# USB_2_High_Speed.net
KiCad netlist of a schematic drawn in Altium Designer
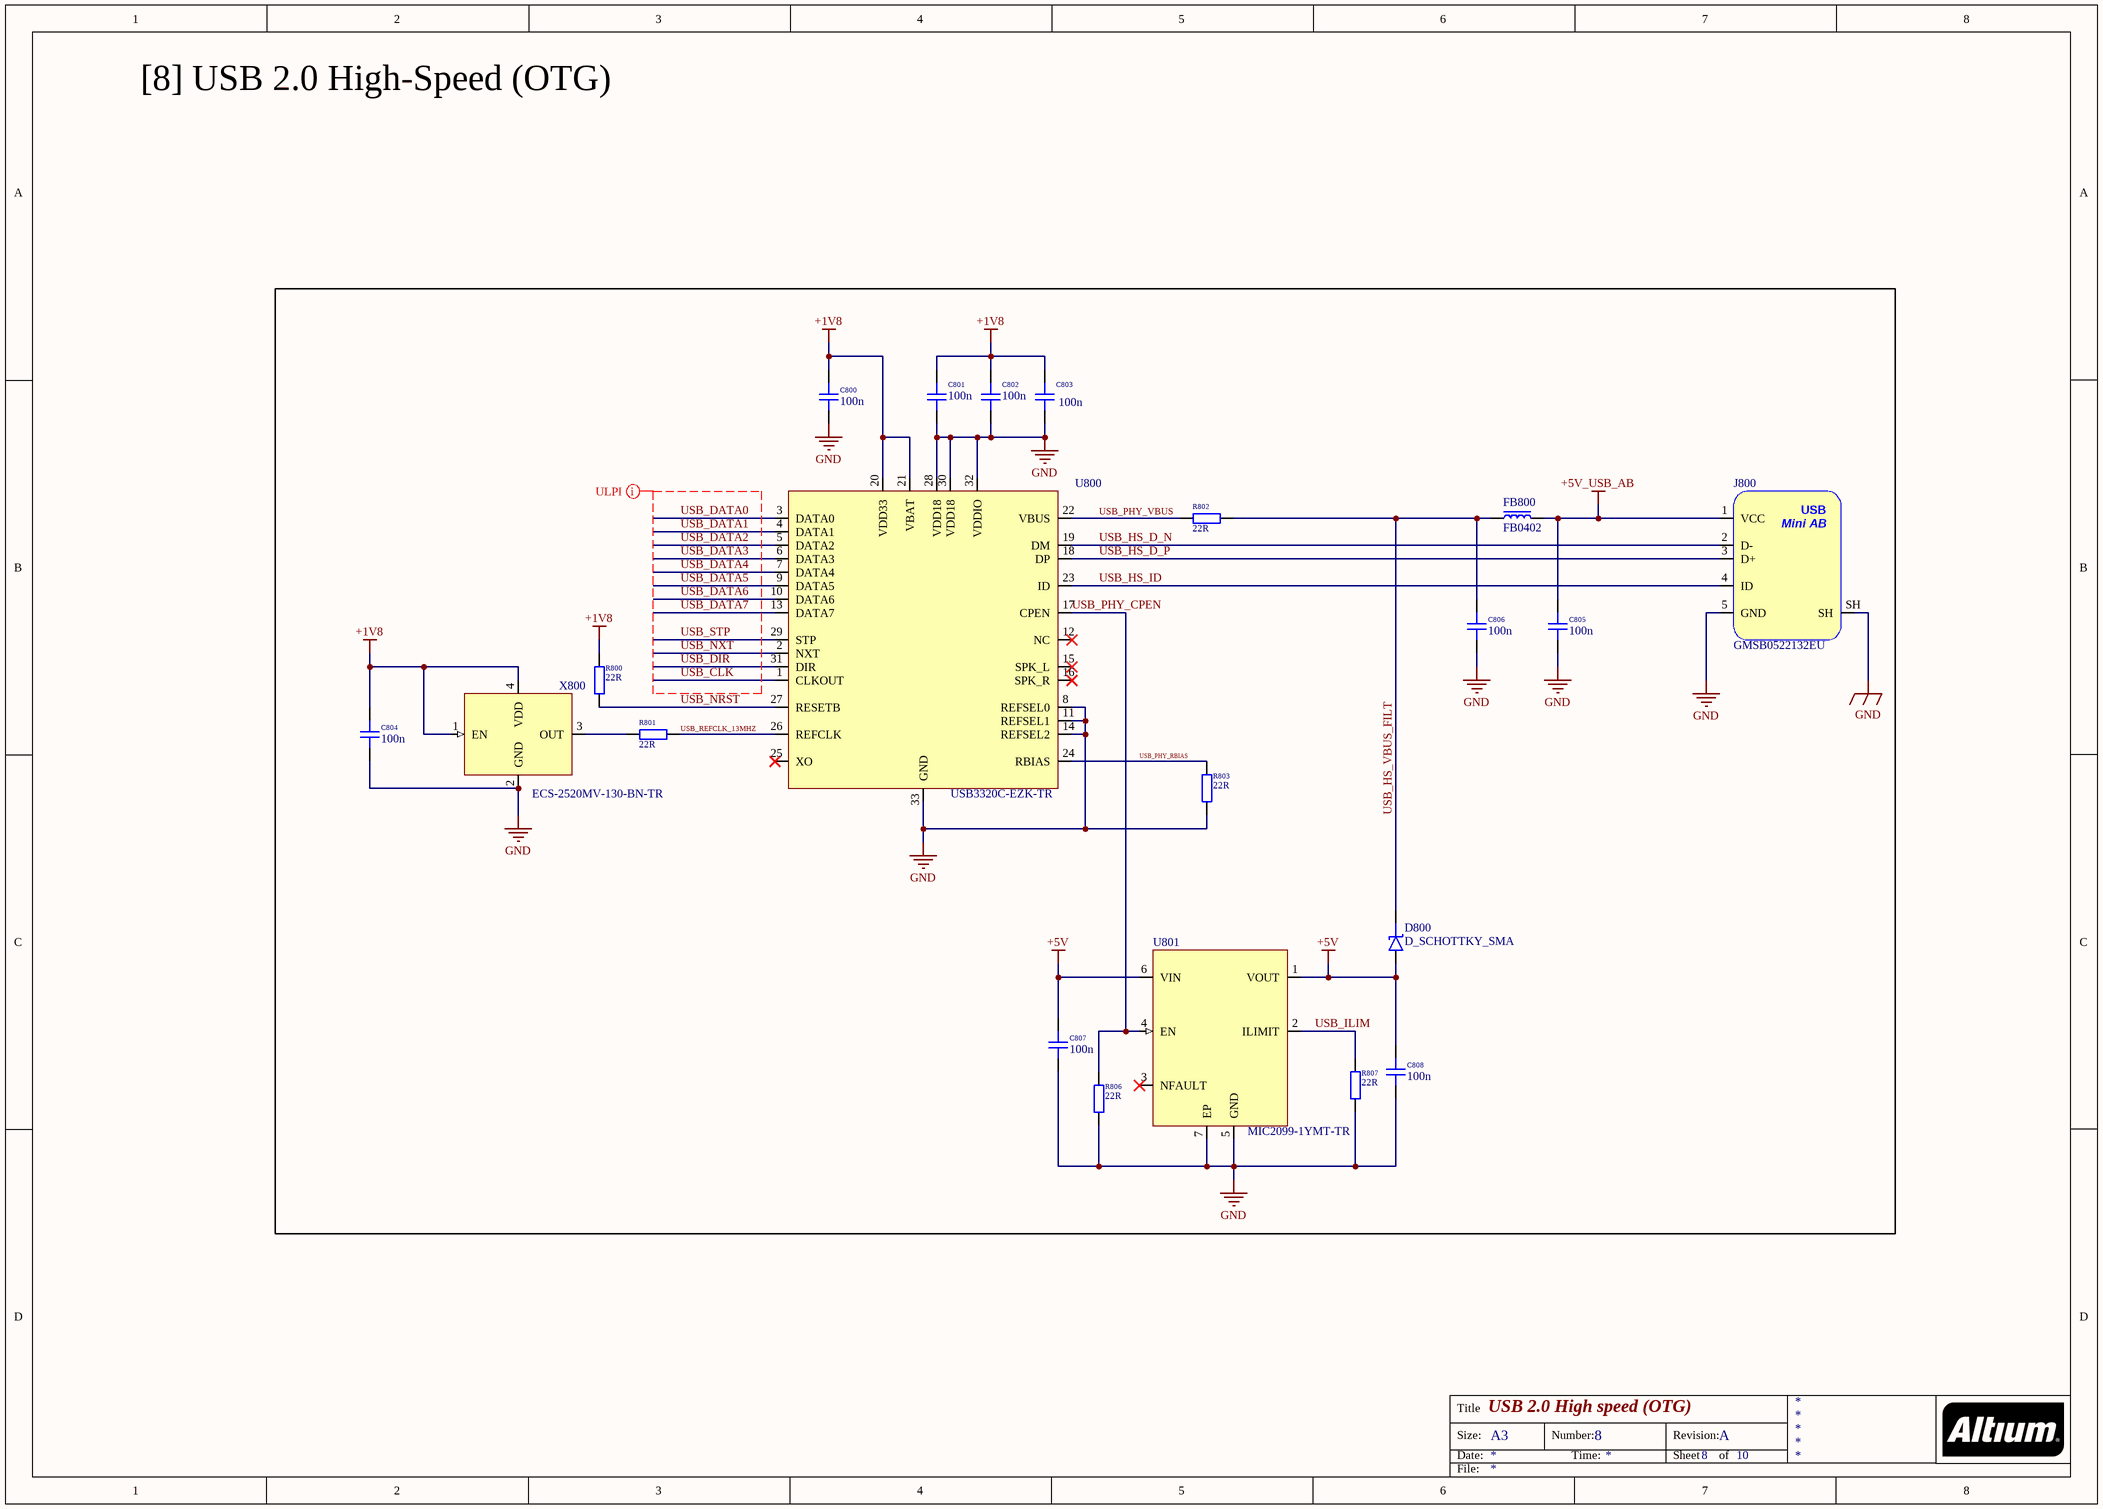
[diagram p0: USB 2 High Speed (OTG).SchDoc]

(export (version "E")
  (design (tool "Eeschema 10.0.6"))
  (components
    (comp (ref "C800")
      (value "100n")
      (footprint "CAP_1210")
      (description "Capacitor SMD 1210")
      (libsource (lib "Schematic-Lib-PhilsLab") (part "CAP_1210"))
    )
    (comp (ref "C801")
      (value "100n")
      (footprint "CAP_1210")
      (description "Capacitor SMD 1210")
      (libsource (lib "Schematic-Lib-PhilsLab") (part "CAP_1210"))
    )
    (comp (ref "C802")
      (value "100n")
      (footprint "CAP_1210")
      (description "Capacitor SMD 1210")
      (libsource (lib "Schematic-Lib-PhilsLab") (part "CAP_1210"))
    )
    (comp (ref "C803")
      (value "100n")
      (footprint "CAP_1210")
      (description "Capacitor SMD 1210")
      (libsource (lib "Schematic-Lib-PhilsLab") (part "CAP_1210"))
    )
    (comp (ref "C804")
      (value "100n")
      (footprint "CAP_1210")
      (description "Capacitor SMD 1210")
      (libsource (lib "Schematic-Lib-PhilsLab") (part "CAP_1210"))
    )
    (comp (ref "C805")
      (value "100n")
      (footprint "CAP_1210")
      (description "Capacitor SMD 1210")
      (libsource (lib "Schematic-Lib-PhilsLab") (part "CAP_1210"))
    )
    (comp (ref "C806")
      (value "100n")
      (footprint "CAP_1210")
      (description "Capacitor SMD 1210")
      (libsource (lib "Schematic-Lib-PhilsLab") (part "CAP_1210"))
    )
    (comp (ref "C807")
      (value "100n")
      (footprint "CAP_1210")
      (description "Capacitor SMD 1210")
      (libsource (lib "Schematic-Lib-PhilsLab") (part "CAP_1210"))
    )
    (comp (ref "C808")
      (value "100n")
      (footprint "CAP_1210")
      (description "Capacitor SMD 1210")
      (libsource (lib "Schematic-Lib-PhilsLab") (part "CAP_1210"))
    )
    (comp (ref "D800")
      (value "D_SCHOTTKY_SMA")
      (footprint "DO-214AC-2 (SMA)")
      (description "Diode Schottky SMD SMA (DO-214AA)")
      (libsource (lib "Schematic-Lib-PhilsLab") (part "D_SCHOTTKY_SMA"))
    )
    (comp (ref "FB800")
      (value "FB0402")
      (footprint "FB_0402")
      (description "Ferrite Bead SMD 0402")
      (libsource (lib "Schematic-Lib-PhilsLab") (part "FB_0402"))
    )
    (comp (ref "J800")
      (value "GMSB0522132EU")
      (footprint "GMSB0522132EU")
      (description "USB 2.0 Mini AB Receptacle Right Angle Through-Hole")
      (fields (field (name "MANUFACTURER") "Amphenol"))
      (libsource (lib "Schematic-Lib-PhilsLab") (part "GMSB0522132EU"))
    )
    (comp (ref "R800")
      (value "22R")
      (footprint "RES_0402")
      (description "Resistor SMD 0402")
      (libsource (lib "Schematic-Lib-PhilsLab") (part "RES_0402"))
    )
    (comp (ref "R801")
      (value "22R")
      (footprint "RES_0402")
      (description "Resistor SMD 0402")
      (libsource (lib "Schematic-Lib-PhilsLab") (part "RES_0402"))
    )
    (comp (ref "R802")
      (value "22R")
      (footprint "RES_0402")
      (description "Resistor SMD 0402")
      (libsource (lib "Schematic-Lib-PhilsLab") (part "RES_0402"))
    )
    (comp (ref "R803")
      (value "22R")
      (footprint "RES_0402")
      (description "Resistor SMD 0402")
      (libsource (lib "Schematic-Lib-PhilsLab") (part "RES_0402"))
    )
    (comp (ref "R806")
      (value "22R")
      (footprint "RES_0402")
      (description "Resistor SMD 0402")
      (libsource (lib "Schematic-Lib-PhilsLab") (part "RES_0402"))
    )
    (comp (ref "R807")
      (value "22R")
      (footprint "RES_0402")
      (description "Resistor SMD 0402")
      (libsource (lib "Schematic-Lib-PhilsLab") (part "RES_0402"))
    )
    (comp (ref "U800")
      (value "USB3320C-EZK-TR")
      (footprint "QFN-32-5x5x0.85mm")
      (description "Hi-Speed USB 2.0 ULPI Transceiver")
      (fields (field (name "MANUFACTURER") "Microchip"))
      (libsource (lib "Schematic-Lib-PhilsLab") (part "USB3320C-EZK-TR"))
    )
    (comp (ref "U801")
      (value "MIC2099-1YMT-TR")
      (footprint "TMLF-6-1_6X1_6")
      (description "Power Distribution Switch Resistor programmable current limit\r\n– 0.1A to 1.1A 2.5V-5.5V")
      (fields (field (name "MANUFACTURER") "Microchip"))
      (libsource (lib "Schematic-Lib-PhilsLab") (part "MIC2099-1YMT-TR"))
    )
    (comp (ref "X800")
      (value "ECS-2520MV-130-BN-TR")
      (footprint "XTAL_2520")
      (fields (field (name "MANUFACTURER") "ECS"))
      (libsource (lib "Schematic-Lib-PhilsLab") (part "ECS-2520MV-130-BN-TR"))
    )
  )
  (nets
    (net (code "1") (name "+1V8") (class "Default")
      (node (ref "C800") (pin "2") (pinfunction "2_2") (pintype "passive"))
      (node (ref "C801") (pin "2") (pinfunction "2_2") (pintype "passive"))
      (node (ref "C802") (pin "2") (pinfunction "2_2") (pintype "passive"))
      (node (ref "C803") (pin "2") (pinfunction "2_2") (pintype "passive"))
      (node (ref "C804") (pin "2") (pinfunction "2_2") (pintype "passive"))
      (node (ref "R800") (pin "1") (pinfunction "1_1") (pintype "passive"))
      (node (ref "U800") (pin "20") (pinfunction "VDD33_20") (pintype "passive"))
      (node (ref "U800") (pin "21") (pinfunction "VBAT_21") (pintype "passive"))
      (node (ref "X800") (pin "1") (pinfunction "EN_1") (pintype "input"))
      (node (ref "X800") (pin "4") (pinfunction "VDD_4") (pintype "power_in"))
    )
    (net (code "2") (name "+5V") (class "Default")
      (node (ref "C807") (pin "2") (pinfunction "2_2") (pintype "passive"))
      (node (ref "C808") (pin "2") (pinfunction "2_2") (pintype "passive"))
      (node (ref "D800") (pin "A") (pinfunction "A_A") (pintype "passive"))
      (node (ref "U801") (pin "1") (pinfunction "VOUT_1") (pintype "power_in"))
      (node (ref "U801") (pin "6") (pinfunction "VIN_6") (pintype "power_in"))
    )
    (net (code "3") (name "+5V_USB_AB") (class "Default")
      (node (ref "C805") (pin "2") (pinfunction "2_2") (pintype "passive"))
      (node (ref "FB800") (pin "2") (pinfunction "2_2") (pintype "passive"))
      (node (ref "J800") (pin "1") (pinfunction "VCC_1") (pintype "power_in"))
    )
    (net (code "4") (name "/USB_CLK") (class "Default")
      (node (ref "U800") (pin "1") (pinfunction "CLKOUT_1") (pintype "passive"))
    )
    (net (code "5") (name "/USB_DATA0") (class "Default")
      (node (ref "U800") (pin "3") (pinfunction "DATA0_3") (pintype "passive"))
    )
    (net (code "6") (name "/USB_DATA1") (class "Default")
      (node (ref "U800") (pin "4") (pinfunction "DATA1_4") (pintype "passive"))
    )
    (net (code "7") (name "/USB_DATA2") (class "Default")
      (node (ref "U800") (pin "5") (pinfunction "DATA2_5") (pintype "passive"))
    )
    (net (code "8") (name "/USB_DATA3") (class "Default")
      (node (ref "U800") (pin "6") (pinfunction "DATA3_6") (pintype "passive"))
    )
    (net (code "9") (name "/USB_DATA4") (class "Default")
      (node (ref "U800") (pin "7") (pinfunction "DATA4_7") (pintype "passive"))
    )
    (net (code "10") (name "/USB_DATA5") (class "Default")
      (node (ref "U800") (pin "9") (pinfunction "DATA5_9") (pintype "passive"))
    )
    (net (code "11") (name "/USB_DATA6") (class "Default")
      (node (ref "U800") (pin "10") (pinfunction "DATA6_10") (pintype "passive"))
    )
    (net (code "12") (name "/USB_DATA7") (class "Default")
      (node (ref "U800") (pin "13") (pinfunction "DATA7_13") (pintype "passive"))
    )
    (net (code "13") (name "/USB_DIR") (class "Default")
      (node (ref "U800") (pin "31") (pinfunction "DIR_31") (pintype "passive"))
    )
    (net (code "14") (name "/USB_HS_D_N") (class "Default")
      (node (ref "J800") (pin "2") (pinfunction "D-_2") (pintype "bidirectional"))
      (node (ref "U800") (pin "19") (pinfunction "DM_19") (pintype "passive"))
    )
    (net (code "15") (name "/USB_HS_D_P") (class "Default")
      (node (ref "J800") (pin "3") (pinfunction "D+_3") (pintype "bidirectional"))
      (node (ref "U800") (pin "18") (pinfunction "DP_18") (pintype "passive"))
    )
    (net (code "16") (name "/USB_HS_ID") (class "Default")
      (node (ref "J800") (pin "4") (pinfunction "ID_4") (pintype "passive"))
      (node (ref "U800") (pin "23") (pinfunction "ID_23") (pintype "passive"))
    )
    (net (code "17") (name "/USB_HS_VBUS_FILT") (class "Default")
      (node (ref "C806") (pin "2") (pinfunction "2_2") (pintype "passive"))
      (node (ref "D800") (pin "K") (pinfunction "K_K") (pintype "passive"))
      (node (ref "FB800") (pin "1") (pinfunction "1_1") (pintype "passive"))
      (node (ref "R802") (pin "1") (pinfunction "1_1") (pintype "passive"))
    )
    (net (code "18") (name "/USB_ILIM") (class "Default")
      (node (ref "R807") (pin "1") (pinfunction "1_1") (pintype "passive"))
      (node (ref "U801") (pin "2") (pinfunction "ILIMIT_2") (pintype "passive"))
    )
    (net (code "19") (name "/USB_NRST") (class "Default")
      (node (ref "R800") (pin "2") (pinfunction "2_2") (pintype "passive"))
      (node (ref "U800") (pin "27") (pinfunction "RESETB_27") (pintype "passive"))
    )
    (net (code "20") (name "/USB_NXT") (class "Default")
      (node (ref "U800") (pin "2") (pinfunction "NXT_2") (pintype "passive"))
    )
    (net (code "21") (name "/USB_PHY_CPEN") (class "Default")
      (node (ref "R806") (pin "1") (pinfunction "1_1") (pintype "passive"))
      (node (ref "U800") (pin "17") (pinfunction "CPEN_17") (pintype "passive"))
      (node (ref "U801") (pin "4") (pinfunction "EN_4") (pintype "input"))
    )
    (net (code "22") (name "/USB_PHY_RBIAS") (class "Default")
      (node (ref "R803") (pin "1") (pinfunction "1_1") (pintype "passive"))
      (node (ref "U800") (pin "24") (pinfunction "RBIAS_24") (pintype "passive"))
    )
    (net (code "23") (name "/USB_PHY_VBUS") (class "Default")
      (node (ref "R802") (pin "2") (pinfunction "2_2") (pintype "passive"))
      (node (ref "U800") (pin "22") (pinfunction "VBUS_22") (pintype "passive"))
    )
    (net (code "24") (name "/USB_REFCLK_13MHZ") (class "Default")
      (node (ref "R801") (pin "1") (pinfunction "1_1") (pintype "passive"))
      (node (ref "U800") (pin "26") (pinfunction "REFCLK_26") (pintype "passive"))
    )
    (net (code "25") (name "/USB_STP") (class "Default")
      (node (ref "U800") (pin "29") (pinfunction "STP_29") (pintype "passive"))
    )
    (net (code "26") (name "GND") (class "Default")
      (node (ref "C800") (pin "1") (pinfunction "1_1") (pintype "passive"))
      (node (ref "C801") (pin "1") (pinfunction "1_1") (pintype "passive"))
      (node (ref "C802") (pin "1") (pinfunction "1_1") (pintype "passive"))
      (node (ref "C803") (pin "1") (pinfunction "1_1") (pintype "passive"))
      (node (ref "C804") (pin "1") (pinfunction "1_1") (pintype "passive"))
      (node (ref "C805") (pin "1") (pinfunction "1_1") (pintype "passive"))
      (node (ref "C806") (pin "1") (pinfunction "1_1") (pintype "passive"))
      (node (ref "C807") (pin "1") (pinfunction "1_1") (pintype "passive"))
      (node (ref "C808") (pin "1") (pinfunction "1_1") (pintype "passive"))
      (node (ref "J800") (pin "5") (pinfunction "GND_5") (pintype "power_in"))
      (node (ref "J800") (pin "SH") (pinfunction "SH_SH") (pintype "power_in"))
      (node (ref "R803") (pin "2") (pinfunction "2_2") (pintype "passive"))
      (node (ref "R806") (pin "2") (pinfunction "2_2") (pintype "passive"))
      (node (ref "R807") (pin "2") (pinfunction "2_2") (pintype "passive"))
      (node (ref "U800") (pin "11") (pinfunction "REFSEL1_11") (pintype "passive"))
      (node (ref "U800") (pin "14") (pinfunction "REFSEL2_14") (pintype "passive"))
      (node (ref "U800") (pin "28") (pinfunction "VDD18_28") (pintype "passive"))
      (node (ref "U800") (pin "30") (pinfunction "VDD18_30") (pintype "passive"))
      (node (ref "U800") (pin "32") (pinfunction "VDDIO_32") (pintype "passive"))
      (node (ref "U800") (pin "33") (pinfunction "GND_33") (pintype "passive"))
      (node (ref "U800") (pin "8") (pinfunction "REFSEL0_8") (pintype "passive"))
      (node (ref "U801") (pin "5") (pinfunction "GND_5") (pintype "power_in"))
      (node (ref "U801") (pin "7") (pinfunction "EP_7") (pintype "power_in"))
      (node (ref "X800") (pin "2") (pinfunction "GND_2") (pintype "power_in"))
    )
    (net (code "27") (name "Net-(X800-OUT)") (class "Default")
      (node (ref "R801") (pin "2") (pinfunction "2_2") (pintype "passive"))
      (node (ref "X800") (pin "3") (pinfunction "OUT_3") (pintype "passive"))
    )
    (net (code "28") (name "unconnected-(U800-NC-Pad12)") (class "Default")
      (node (ref "U800") (pin "12") (pinfunction "NC_12") (pintype "passive+no_connect"))
    )
    (net (code "29") (name "unconnected-(U800-SPK_L-Pad15)") (class "Default")
      (node (ref "U800") (pin "15") (pinfunction "SPK_L_15") (pintype "passive+no_connect"))
    )
    (net (code "30") (name "unconnected-(U800-SPK_R-Pad16)") (class "Default")
      (node (ref "U800") (pin "16") (pinfunction "SPK_R_16") (pintype "passive+no_connect"))
    )
    (net (code "31") (name "unconnected-(U800-XO-Pad25)") (class "Default")
      (node (ref "U800") (pin "25") (pinfunction "XO_25") (pintype "passive+no_connect"))
    )
    (net (code "32") (name "unconnected-(U801-NFAULT-Pad3)") (class "Default")
      (node (ref "U801") (pin "3") (pinfunction "NFAULT_3") (pintype "open_collector+no_connect"))
    )
  )
)
